# lantern.net
KiCad netlist of a schematic drawn in EAGLE
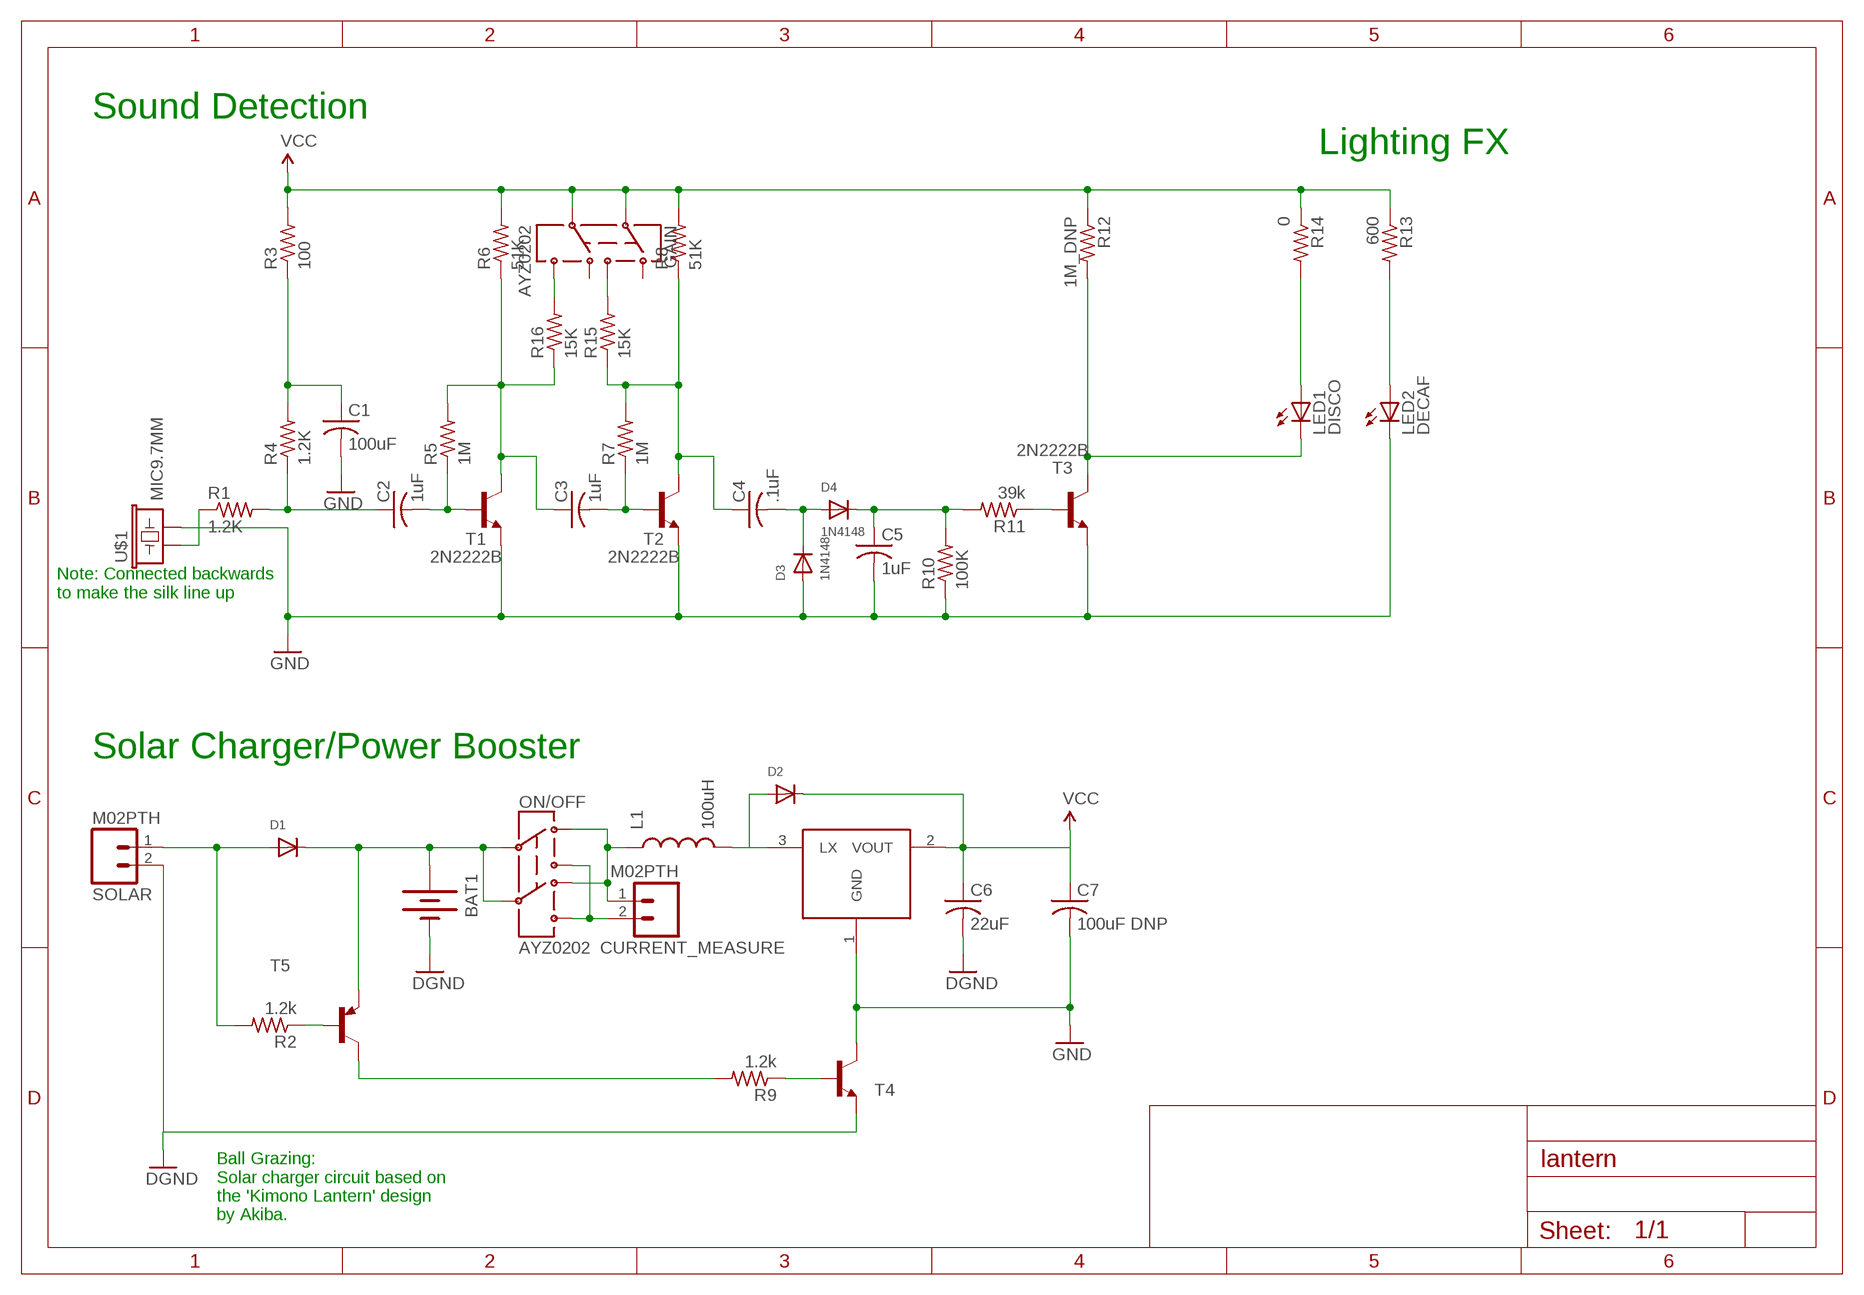
[diagram p0: schematic, sheet 1]

(export (version "E")
  (design (tool "Eeschema 10.0.6"))
  (components
    (comp (ref "BAT1")
      (value "BATTERYAAA")
      (footprint "eagle-import:BATTERY-AAA")
      (libsource (lib "eagle-import") (part "BATTERYAAA"))
    )
    (comp (ref "C1")
      (value "100uF")
      (footprint "eagle-import:C1210")
      (libsource (lib "eagle-import") (part "C-USC1210"))
    )
    (comp (ref "C2")
      (value "1uF")
      (footprint "eagle-import:C0603")
      (libsource (lib "eagle-import") (part "C-USC0603"))
    )
    (comp (ref "C3")
      (value "1uF")
      (footprint "eagle-import:C0603")
      (libsource (lib "eagle-import") (part "C-USC0603"))
    )
    (comp (ref "C4")
      (value ".1uF")
      (footprint "eagle-import:C0603")
      (libsource (lib "eagle-import") (part "C-USC0603"))
    )
    (comp (ref "C5")
      (value "1uF")
      (footprint "eagle-import:C0603")
      (libsource (lib "eagle-import") (part "C-USC0603"))
    )
    (comp (ref "C6")
      (value "22uF")
      (footprint "eagle-import:C0603")
      (libsource (lib "eagle-import") (part "C-USC0603"))
    )
    (comp (ref "C7")
      (value "100uF DNP")
      (footprint "eagle-import:C1210")
      (libsource (lib "eagle-import") (part "C-USC1210"))
    )
    (comp (ref "CURRENT_MEASURE")
      (value "M02PTH")
      (footprint "eagle-import:1X02")
      (libsource (lib "eagle-import") (part "M02PTH"))
    )
    (comp (ref "D1")
      (value "DIODESOT23_REFLOW")
      (footprint "eagle-import:SOT23-R")
      (libsource (lib "eagle-import") (part "DIODESOT23_REFLOW"))
    )
    (comp (ref "D2")
      (value "DIODESOT23_REFLOW")
      (footprint "eagle-import:SOT23-R")
      (libsource (lib "eagle-import") (part "DIODESOT23_REFLOW"))
    )
    (comp (ref "D3")
      (value "1N4148")
      (footprint "eagle-import:SOT23-R")
      (libsource (lib "eagle-import") (part "DIODESOT23_REFLOW"))
    )
    (comp (ref "D4")
      (value "1N4148")
      (footprint "eagle-import:SOT23-R")
      (libsource (lib "eagle-import") (part "DIODESOT23_REFLOW"))
    )
    (comp (ref "GAIN")
      (value "AYZ0202")
      (footprint "eagle-import:AYZ0202")
      (libsource (lib "eagle-import") (part "AYZ0202"))
    )
    (comp (ref "L1")
      (value "100uH")
      (footprint "eagle-import:0805")
      (libsource (lib "eagle-import") (part "INDUCTOR0805"))
    )
    (comp (ref "LED1")
      (value "DISCO")
      (footprint "eagle-import:LED5MM")
      (libsource (lib "eagle-import") (part "LED5MM"))
    )
    (comp (ref "LED2")
      (value "DECAF")
      (footprint "eagle-import:LED5MM")
      (libsource (lib "eagle-import") (part "LED5MM"))
    )
    (comp (ref "ON/OFF")
      (value "AYZ0202")
      (footprint "eagle-import:AYZ0202")
      (libsource (lib "eagle-import") (part "AYZ0202"))
    )
    (comp (ref "R1")
      (value "1.2K")
      (footprint "eagle-import:R0603")
      (libsource (lib "eagle-import") (part "R-US_R0603"))
    )
    (comp (ref "R2")
      (value "1.2k")
      (footprint "eagle-import:R0603")
      (libsource (lib "eagle-import") (part "R-US_R0603"))
    )
    (comp (ref "R3")
      (value "100")
      (footprint "eagle-import:R0603")
      (libsource (lib "eagle-import") (part "R-US_R0603"))
    )
    (comp (ref "R4")
      (value "1.2K")
      (footprint "eagle-import:R0603")
      (libsource (lib "eagle-import") (part "R-US_R0603"))
    )
    (comp (ref "R5")
      (value "1M")
      (footprint "eagle-import:R0603")
      (libsource (lib "eagle-import") (part "R-US_R0603"))
    )
    (comp (ref "R6")
      (value "51K")
      (footprint "eagle-import:R0603")
      (libsource (lib "eagle-import") (part "R-US_R0603"))
    )
    (comp (ref "R7")
      (value "1M")
      (footprint "eagle-import:R0603")
      (libsource (lib "eagle-import") (part "R-US_R0603"))
    )
    (comp (ref "R8")
      (value "51K")
      (footprint "eagle-import:R0603")
      (libsource (lib "eagle-import") (part "R-US_R0603"))
    )
    (comp (ref "R9")
      (value "1.2k")
      (footprint "eagle-import:R0603")
      (libsource (lib "eagle-import") (part "R-US_R0603"))
    )
    (comp (ref "R10")
      (value "100K")
      (footprint "eagle-import:R0603")
      (libsource (lib "eagle-import") (part "R-US_R0603"))
    )
    (comp (ref "R11")
      (value "39k")
      (footprint "eagle-import:R0603")
      (libsource (lib "eagle-import") (part "R-US_R0603"))
    )
    (comp (ref "R12")
      (value "1M_DNP")
      (footprint "eagle-import:R0603")
      (libsource (lib "eagle-import") (part "R-US_R0603"))
    )
    (comp (ref "R13")
      (value "600")
      (footprint "eagle-import:R0603")
      (libsource (lib "eagle-import") (part "R-US_R0603"))
    )
    (comp (ref "R14")
      (value "0")
      (footprint "eagle-import:R0603")
      (libsource (lib "eagle-import") (part "R-US_R0603"))
    )
    (comp (ref "R15")
      (value "15K")
      (footprint "eagle-import:R0603")
      (libsource (lib "eagle-import") (part "R-US_R0603"))
    )
    (comp (ref "R16")
      (value "15K")
      (footprint "eagle-import:R0603")
      (libsource (lib "eagle-import") (part "R-US_R0603"))
    )
    (comp (ref "SOLAR")
      (value "M02PTH")
      (footprint "eagle-import:1X02")
      (libsource (lib "eagle-import") (part "M02PTH"))
    )
    (comp (ref "T1")
      (value "2N2222B")
      (footprint "eagle-import:SOT23")
      (libsource (lib "eagle-import") (part "2N2222B"))
    )
    (comp (ref "T2")
      (value "2N2222B")
      (footprint "eagle-import:SOT23")
      (libsource (lib "eagle-import") (part "2N2222B"))
    )
    (comp (ref "T3")
      (value "2N2222B")
      (footprint "eagle-import:SOT23")
      (libsource (lib "eagle-import") (part "2N2222B"))
    )
    (comp (ref "T4")
      (value "2N2222B")
      (footprint "eagle-import:SOT23")
      (libsource (lib "eagle-import") (part "2N2222B"))
    )
    (comp (ref "T5")
      (value "2N2907B")
      (footprint "eagle-import:SOT23")
      (libsource (lib "eagle-import") (part "2N2907B"))
    )
    (comp (ref "U$1")
      (value "MIC9.7MM")
      (footprint "eagle-import:MIC-9.7MM")
      (libsource (lib "eagle-import") (part "MIC9.7MM"))
    )
    (comp (ref "U2")
      (value "HT7733A")
      (footprint "eagle-import:SOT89")
      (libsource (lib "eagle-import") (part "HT7733A"))
    )
  )
  (nets
    (net (code "1") (name "DGND") (class "Default")
      (node (ref "BAT1") (pin "GND@1") (pinfunction "-_GND@1") (pintype "power_in"))
      (node (ref "C6") (pin "2") (pinfunction "2_2") (pintype "passive"))
      (node (ref "SOLAR") (pin "2") (pinfunction "2_2") (pintype "passive"))
      (node (ref "T4") (pin "2") (pinfunction "E_2") (pintype "passive"))
    )
    (net (code "2") (name "GND") (class "Default")
      (node (ref "C1") (pin "2") (pinfunction "2_2") (pintype "passive"))
      (node (ref "C5") (pin "2") (pinfunction "2_2") (pintype "passive"))
      (node (ref "C7") (pin "2") (pinfunction "2_2") (pintype "passive"))
      (node (ref "D3") (pin "1") (pinfunction "A_1") (pintype "passive"))
      (node (ref "LED2") (pin "K") (pinfunction "C_K") (pintype "passive"))
      (node (ref "R10") (pin "1") (pinfunction "1_1") (pintype "passive"))
      (node (ref "T1") (pin "2") (pinfunction "E_2") (pintype "passive"))
      (node (ref "T2") (pin "2") (pinfunction "E_2") (pintype "passive"))
      (node (ref "T3") (pin "2") (pinfunction "E_2") (pintype "passive"))
      (node (ref "T4") (pin "3") (pinfunction "C_3") (pintype "passive"))
      (node (ref "U$1") (pin "2") (pinfunction "2_2") (pintype "passive"))
      (node (ref "U2") (pin "1") (pinfunction "GND_1") (pintype "power_in"))
    )
    (net (code "3") (name "Net-(BAT1-+)") (class "Default")
      (node (ref "BAT1") (pin "PWR@1") (pinfunction "+_PWR@1") (pintype "power_in"))
      (node (ref "D1") (pin "3") (pinfunction "C_3") (pintype "passive"))
      (node (ref "ON/OFF") (pin "2") (pinfunction "2_2") (pintype "bidirectional"))
      (node (ref "ON/OFF") (pin "5") (pinfunction "5_5") (pintype "bidirectional"))
      (node (ref "T5") (pin "2") (pinfunction "E_2") (pintype "passive"))
    )
    (net (code "4") (name "Net-(C1-Pad1)") (class "Default")
      (node (ref "C1") (pin "1") (pinfunction "1_1") (pintype "passive"))
      (node (ref "R3") (pin "1") (pinfunction "1_1") (pintype "passive"))
      (node (ref "R4") (pin "2") (pinfunction "2_2") (pintype "passive"))
    )
    (net (code "5") (name "Net-(C2-Pad1)") (class "Default")
      (node (ref "C2") (pin "1") (pinfunction "1_1") (pintype "passive"))
      (node (ref "R1") (pin "2") (pinfunction "2_2") (pintype "passive"))
      (node (ref "R4") (pin "1") (pinfunction "1_1") (pintype "passive"))
    )
    (net (code "6") (name "Net-(D1-A)") (class "Default")
      (node (ref "D1") (pin "1") (pinfunction "A_1") (pintype "passive"))
      (node (ref "R2") (pin "2") (pinfunction "2_2") (pintype "passive"))
      (node (ref "SOLAR") (pin "1") (pinfunction "1_1") (pintype "passive"))
    )
    (net (code "7") (name "Net-(D2-A)") (class "Default")
      (node (ref "D2") (pin "1") (pinfunction "A_1") (pintype "passive"))
      (node (ref "L1") (pin "2") (pinfunction "2_2") (pintype "passive"))
      (node (ref "U2") (pin "3") (pinfunction "LX_3") (pintype "power_in"))
    )
    (net (code "8") (name "Net-(D3-C)") (class "Default")
      (node (ref "C4") (pin "2") (pinfunction "2_2") (pintype "passive"))
      (node (ref "D3") (pin "3") (pinfunction "C_3") (pintype "passive"))
      (node (ref "D4") (pin "1") (pinfunction "A_1") (pintype "passive"))
    )
    (net (code "9") (name "Net-(D4-C)") (class "Default")
      (node (ref "C5") (pin "1") (pinfunction "1_1") (pintype "passive"))
      (node (ref "D4") (pin "3") (pinfunction "C_3") (pintype "passive"))
      (node (ref "R10") (pin "2") (pinfunction "2_2") (pintype "passive"))
      (node (ref "R11") (pin "2") (pinfunction "2_2") (pintype "passive"))
    )
    (net (code "10") (name "Net-(GAIN-3)") (class "Default")
      (node (ref "GAIN") (pin "1") (pinfunction "3_1") (pintype "bidirectional"))
      (node (ref "R15") (pin "2") (pinfunction "2_2") (pintype "passive"))
    )
    (net (code "11") (name "Net-(GAIN-6)") (class "Default")
      (node (ref "GAIN") (pin "4") (pinfunction "6_4") (pintype "bidirectional"))
      (node (ref "R16") (pin "2") (pinfunction "2_2") (pintype "passive"))
    )
    (net (code "12") (name "Net-(LED1-C)") (class "Default")
      (node (ref "LED1") (pin "K") (pinfunction "C_K") (pintype "passive"))
      (node (ref "R12") (pin "2") (pinfunction "2_2") (pintype "passive"))
      (node (ref "T3") (pin "3") (pinfunction "C_3") (pintype "passive"))
    )
    (net (code "13") (name "Net-(LED1-PadA)") (class "Default")
      (node (ref "LED1") (pin "A") (pinfunction "A_A") (pintype "passive"))
      (node (ref "R14") (pin "2") (pinfunction "2_2") (pintype "passive"))
    )
    (net (code "14") (name "Net-(LED2-PadA)") (class "Default")
      (node (ref "LED2") (pin "A") (pinfunction "A_A") (pintype "passive"))
      (node (ref "R13") (pin "2") (pinfunction "2_2") (pintype "passive"))
    )
    (net (code "15") (name "Net-(ON/OFF-1)") (class "Default")
      (node (ref "CURRENT_MEASURE") (pin "1") (pinfunction "1_1") (pintype "passive"))
      (node (ref "L1") (pin "1") (pinfunction "1_1") (pintype "passive"))
      (node (ref "ON/OFF") (pin "3") (pinfunction "1_3") (pintype "bidirectional"))
      (node (ref "ON/OFF") (pin "6") (pinfunction "4_6") (pintype "bidirectional"))
    )
    (net (code "16") (name "Net-(ON/OFF-3)") (class "Default")
      (node (ref "CURRENT_MEASURE") (pin "2") (pinfunction "2_2") (pintype "passive"))
      (node (ref "ON/OFF") (pin "1") (pinfunction "3_1") (pintype "bidirectional"))
      (node (ref "ON/OFF") (pin "4") (pinfunction "6_4") (pintype "bidirectional"))
    )
    (net (code "17") (name "Net-(R1-Pad1)") (class "Default")
      (node (ref "R1") (pin "1") (pinfunction "1_1") (pintype "passive"))
      (node (ref "U$1") (pin "1") (pinfunction "1_1") (pintype "passive"))
    )
    (net (code "18") (name "Net-(T1-B)") (class "Default")
      (node (ref "C2") (pin "2") (pinfunction "2_2") (pintype "passive"))
      (node (ref "R5") (pin "1") (pinfunction "1_1") (pintype "passive"))
      (node (ref "T1") (pin "1") (pinfunction "B_1") (pintype "passive"))
    )
    (net (code "19") (name "Net-(T1-C)") (class "Default")
      (node (ref "C3") (pin "1") (pinfunction "1_1") (pintype "passive"))
      (node (ref "R16") (pin "1") (pinfunction "1_1") (pintype "passive"))
      (node (ref "R5") (pin "2") (pinfunction "2_2") (pintype "passive"))
      (node (ref "R6") (pin "1") (pinfunction "1_1") (pintype "passive"))
      (node (ref "T1") (pin "3") (pinfunction "C_3") (pintype "passive"))
    )
    (net (code "20") (name "Net-(T2-B)") (class "Default")
      (node (ref "C3") (pin "2") (pinfunction "2_2") (pintype "passive"))
      (node (ref "R7") (pin "1") (pinfunction "1_1") (pintype "passive"))
      (node (ref "T2") (pin "1") (pinfunction "B_1") (pintype "passive"))
    )
    (net (code "21") (name "Net-(T2-C)") (class "Default")
      (node (ref "C4") (pin "1") (pinfunction "1_1") (pintype "passive"))
      (node (ref "R15") (pin "1") (pinfunction "1_1") (pintype "passive"))
      (node (ref "R7") (pin "2") (pinfunction "2_2") (pintype "passive"))
      (node (ref "R8") (pin "1") (pinfunction "1_1") (pintype "passive"))
      (node (ref "T2") (pin "3") (pinfunction "C_3") (pintype "passive"))
    )
    (net (code "22") (name "Net-(T3-B)") (class "Default")
      (node (ref "R11") (pin "1") (pinfunction "1_1") (pintype "passive"))
      (node (ref "T3") (pin "1") (pinfunction "B_1") (pintype "passive"))
    )
    (net (code "23") (name "Net-(T4-B)") (class "Default")
      (node (ref "R9") (pin "1") (pinfunction "1_1") (pintype "passive"))
      (node (ref "T4") (pin "1") (pinfunction "B_1") (pintype "passive"))
    )
    (net (code "24") (name "Net-(T5-B)") (class "Default")
      (node (ref "R2") (pin "1") (pinfunction "1_1") (pintype "passive"))
      (node (ref "T5") (pin "1") (pinfunction "B_1") (pintype "passive"))
    )
    (net (code "25") (name "Net-(T5-C)") (class "Default")
      (node (ref "R9") (pin "2") (pinfunction "2_2") (pintype "passive"))
      (node (ref "T5") (pin "3") (pinfunction "C_3") (pintype "passive"))
    )
    (net (code "26") (name "VCC") (class "Default")
      (node (ref "C6") (pin "1") (pinfunction "1_1") (pintype "passive"))
      (node (ref "C7") (pin "1") (pinfunction "1_1") (pintype "passive"))
      (node (ref "D2") (pin "3") (pinfunction "C_3") (pintype "passive"))
      (node (ref "GAIN") (pin "2") (pinfunction "2_2") (pintype "bidirectional"))
      (node (ref "GAIN") (pin "5") (pinfunction "5_5") (pintype "bidirectional"))
      (node (ref "R12") (pin "1") (pinfunction "1_1") (pintype "passive"))
      (node (ref "R13") (pin "1") (pinfunction "1_1") (pintype "passive"))
      (node (ref "R14") (pin "1") (pinfunction "1_1") (pintype "passive"))
      (node (ref "R3") (pin "2") (pinfunction "2_2") (pintype "passive"))
      (node (ref "R6") (pin "2") (pinfunction "2_2") (pintype "passive"))
      (node (ref "R8") (pin "2") (pinfunction "2_2") (pintype "passive"))
      (node (ref "U2") (pin "2") (pinfunction "VOUT_2") (pintype "power_in"))
    )
    (net (code "27") (name "unconnected-(GAIN-1-Pad3)") (class "Default")
      (node (ref "GAIN") (pin "3") (pinfunction "1_3") (pintype "bidirectional"))
    )
    (net (code "28") (name "unconnected-(GAIN-4-Pad6)") (class "Default")
      (node (ref "GAIN") (pin "6") (pinfunction "4_6") (pintype "bidirectional"))
    )
  )
)
